# Breakout.net
KiCad netlist of a schematic drawn in Altium Designer
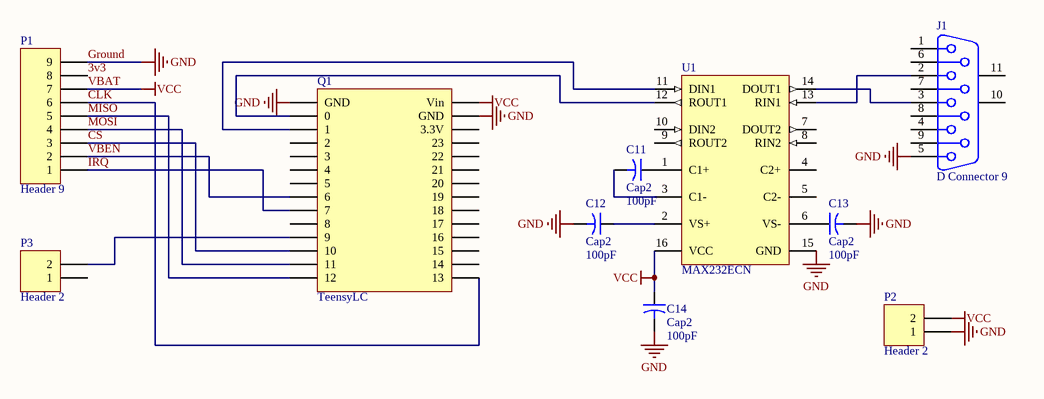
[diagram p0: Breakout.SchDoc]

(export (version "E")
  (design (tool "Eeschema 10.0.6"))
  (components
    (comp (ref "C11")
      (value "Cap2")
      (footprint "CAPR5-4X5")
      (description "Capacitor")
      (fields (field (name "ALTIUM_VALUE") "100pF") (field (name "PUBLISHER") "Altium Limited"))
      (libsource (lib "Miscellaneous Devices") (part "Cap2"))
    )
    (comp (ref "C12")
      (value "Cap2")
      (footprint "CAPR5-4X5")
      (description "Capacitor")
      (fields (field (name "ALTIUM_VALUE") "100pF") (field (name "PUBLISHER") "Altium Limited"))
      (libsource (lib "Miscellaneous Devices") (part "Cap2"))
    )
    (comp (ref "C13")
      (value "Cap2")
      (footprint "CAPR5-4X5")
      (description "Capacitor")
      (fields (field (name "ALTIUM_VALUE") "100pF") (field (name "PUBLISHER") "Altium Limited"))
      (libsource (lib "Miscellaneous Devices") (part "Cap2"))
    )
    (comp (ref "C14")
      (value "Cap2")
      (footprint "CAPR5-4X5")
      (description "Capacitor")
      (fields (field (name "ALTIUM_VALUE") "100pF") (field (name "PUBLISHER") "Altium Limited"))
      (libsource (lib "Miscellaneous Devices") (part "Cap2"))
    )
    (comp (ref "J1")
      (value "D Connector 9")
      (footprint "DSUB1.385-2H9")
      (description "Receptacle Assembly, 9 Position, Right Angle")
      (fields (field (name "PUBLISHER") "Altium Limited"))
      (libsource (lib "Miscellaneous Connectors") (part "D Connector 9"))
    )
    (comp (ref "P1")
      (value "Header 9")
      (footprint "HDR1X9")
      (description "Header, 9-Pin")
      (fields (field (name "PUBLISHER") "Altium Limited"))
      (libsource (lib "Miscellaneous Connectors") (part "Header 9"))
    )
    (comp (ref "P2")
      (value "Header 2")
      (footprint "HDR1X2")
      (description "Header, 2-Pin")
      (fields (field (name "PUBLISHER") "Altium Limited"))
      (libsource (lib "Miscellaneous Connectors") (part "Header 2"))
    )
    (comp (ref "P3")
      (value "Header 2")
      (footprint "HDR1X2")
      (description "Header, 2-Pin")
      (fields (field (name "PUBLISHER") "Altium Limited"))
      (libsource (lib "Miscellaneous Connectors") (part "Header 2"))
    )
    (comp (ref "Q1")
      (value "TeensyLC")
      (footprint "TeensyLC")
      (libsource (lib "Custom_Components") (part "TeensyLC"))
    )
    (comp (ref "U1")
      (value "MAX232ECN")
      (footprint "TI-N16")
      (libsource (lib "Texas Instruments Interface RS-232") (part "MAX232ECN"))
    )
  )
  (nets
    (net (code "1") (name "/3v3") (class "Default")
      (node (ref "P1") (pin "8") (pinfunction "8_8") (pintype "passive"))
    )
    (net (code "2") (name "/CLK") (class "Default")
      (node (ref "P1") (pin "6") (pinfunction "6_6") (pintype "passive"))
      (node (ref "Q1") (pin "15") (pinfunction "13_15") (pintype "passive"))
    )
    (net (code "3") (name "/CS") (class "Default")
      (node (ref "P1") (pin "3") (pinfunction "3_3") (pintype "passive"))
      (node (ref "Q1") (pin "12") (pinfunction "10_12") (pintype "passive"))
    )
    (net (code "4") (name "/IRQ") (class "Default")
      (node (ref "P1") (pin "1") (pinfunction "1_1") (pintype "passive"))
      (node (ref "Q1") (pin "9") (pinfunction "7_9") (pintype "passive"))
    )
    (net (code "5") (name "/MISO") (class "Default")
      (node (ref "P1") (pin "5") (pinfunction "5_5") (pintype "passive"))
      (node (ref "Q1") (pin "14") (pinfunction "12_14") (pintype "passive"))
    )
    (net (code "6") (name "/MOSI") (class "Default")
      (node (ref "P1") (pin "4") (pinfunction "4_4") (pintype "passive"))
      (node (ref "Q1") (pin "13") (pinfunction "11_13") (pintype "passive"))
    )
    (net (code "7") (name "/VBEN") (class "Default")
      (node (ref "P1") (pin "2") (pinfunction "2_2") (pintype "passive"))
      (node (ref "Q1") (pin "8") (pinfunction "6_8") (pintype "passive"))
    )
    (net (code "8") (name "GND") (class "Default")
      (node (ref "C12") (pin "2") (pinfunction "2_2") (pintype "passive"))
      (node (ref "C13") (pin "2") (pinfunction "2_2") (pintype "passive"))
      (node (ref "C14") (pin "2") (pinfunction "2_2") (pintype "passive"))
      (node (ref "J1") (pin "5") (pinfunction "5_5") (pintype "passive"))
      (node (ref "P1") (pin "9") (pinfunction "9_9") (pintype "passive"))
      (node (ref "P2") (pin "1") (pinfunction "1_1") (pintype "passive"))
      (node (ref "Q1") (pin "1") (pinfunction "GND_1") (pintype "passive"))
      (node (ref "Q1") (pin "27") (pinfunction "GND_27") (pintype "passive"))
      (node (ref "U1") (pin "15") (pinfunction "GND_15") (pintype "power_in"))
    )
    (net (code "9") (name "Net-(Q1-0)") (class "Default")
      (node (ref "Q1") (pin "2") (pinfunction "0_2") (pintype "passive"))
      (node (ref "U1") (pin "12") (pinfunction "ROUT1_12") (pintype "output"))
    )
    (net (code "10") (name "Net-(Q1-1)") (class "Default")
      (node (ref "Q1") (pin "3") (pinfunction "1_3") (pintype "passive"))
      (node (ref "U1") (pin "11") (pinfunction "DIN1_11") (pintype "input"))
    )
    (net (code "11") (name "Net-(Q1-9)") (class "Default")
      (node (ref "P3") (pin "2") (pinfunction "2_2") (pintype "passive"))
      (node (ref "Q1") (pin "11") (pinfunction "9_11") (pintype "passive"))
    )
    (net (code "12") (name "Net-(U1-C1+)") (class "Default")
      (node (ref "C11") (pin "1") (pinfunction "1_1") (pintype "passive"))
      (node (ref "U1") (pin "1") (pinfunction "C1+_1") (pintype "passive"))
    )
    (net (code "13") (name "Net-(U1-C1-)") (class "Default")
      (node (ref "C11") (pin "2") (pinfunction "2_2") (pintype "passive"))
      (node (ref "U1") (pin "3") (pinfunction "C1-_3") (pintype "passive"))
    )
    (net (code "14") (name "Net-(U1-DOUT1)") (class "Default")
      (node (ref "J1") (pin "3") (pinfunction "3_3") (pintype "passive"))
      (node (ref "U1") (pin "14") (pinfunction "DOUT1_14") (pintype "output"))
    )
    (net (code "15") (name "Net-(U1-RIN1)") (class "Default")
      (node (ref "J1") (pin "2") (pinfunction "2_2") (pintype "passive"))
      (node (ref "U1") (pin "13") (pinfunction "RIN1_13") (pintype "input"))
    )
    (net (code "16") (name "Net-(U1-VS+)") (class "Default")
      (node (ref "C12") (pin "1") (pinfunction "1_1") (pintype "passive"))
      (node (ref "U1") (pin "2") (pinfunction "VS+_2") (pintype "power_in"))
    )
    (net (code "17") (name "Net-(U1-VS-)") (class "Default")
      (node (ref "C13") (pin "1") (pinfunction "1_1") (pintype "passive"))
      (node (ref "U1") (pin "6") (pinfunction "VS-_6") (pintype "power_in"))
    )
    (net (code "18") (name "VCC") (class "Default")
      (node (ref "C14") (pin "1") (pinfunction "1_1") (pintype "passive"))
      (node (ref "P1") (pin "7") (pinfunction "7_7") (pintype "passive"))
      (node (ref "P2") (pin "2") (pinfunction "2_2") (pintype "passive"))
      (node (ref "Q1") (pin "28") (pinfunction "Vin_28") (pintype "passive"))
      (node (ref "U1") (pin "16") (pinfunction "VCC_16") (pintype "power_in"))
    )
    (net (code "19") (name "unconnected-(J1-MH1-Pad10)") (class "Default")
      (node (ref "J1") (pin "10") (pinfunction "MH1_10") (pintype "passive"))
    )
    (net (code "20") (name "unconnected-(J1-MH2-Pad11)") (class "Default")
      (node (ref "J1") (pin "11") (pinfunction "MH2_11") (pintype "passive"))
    )
    (net (code "21") (name "unconnected-(J1-Pad1)") (class "Default")
      (node (ref "J1") (pin "1") (pinfunction "1_1") (pintype "passive"))
    )
    (net (code "22") (name "unconnected-(J1-Pad4)") (class "Default")
      (node (ref "J1") (pin "4") (pinfunction "4_4") (pintype "passive"))
    )
    (net (code "23") (name "unconnected-(J1-Pad6)") (class "Default")
      (node (ref "J1") (pin "6") (pinfunction "6_6") (pintype "passive"))
    )
    (net (code "24") (name "unconnected-(J1-Pad7)") (class "Default")
      (node (ref "J1") (pin "7") (pinfunction "7_7") (pintype "passive"))
    )
    (net (code "25") (name "unconnected-(J1-Pad8)") (class "Default")
      (node (ref "J1") (pin "8") (pinfunction "8_8") (pintype "passive"))
    )
    (net (code "26") (name "unconnected-(J1-Pad9)") (class "Default")
      (node (ref "J1") (pin "9") (pinfunction "9_9") (pintype "passive"))
    )
    (net (code "27") (name "unconnected-(P3-Pad1)") (class "Default")
      (node (ref "P3") (pin "1") (pinfunction "1_1") (pintype "passive"))
    )
    (net (code "28") (name "unconnected-(Q1-2-Pad4)") (class "Default")
      (node (ref "Q1") (pin "4") (pinfunction "2_4") (pintype "passive"))
    )
    (net (code "29") (name "unconnected-(Q1-3-Pad5)") (class "Default")
      (node (ref "Q1") (pin "5") (pinfunction "3_5") (pintype "passive"))
    )
    (net (code "30") (name "unconnected-(Q1-3.3V-Pad26)") (class "Default")
      (node (ref "Q1") (pin "26") (pinfunction "3.3V_26") (pintype "passive"))
    )
    (net (code "31") (name "unconnected-(Q1-4-Pad6)") (class "Default")
      (node (ref "Q1") (pin "6") (pinfunction "4_6") (pintype "passive"))
    )
    (net (code "32") (name "unconnected-(Q1-5-Pad7)") (class "Default")
      (node (ref "Q1") (pin "7") (pinfunction "5_7") (pintype "passive"))
    )
    (net (code "33") (name "unconnected-(Q1-8-Pad10)") (class "Default")
      (node (ref "Q1") (pin "10") (pinfunction "8_10") (pintype "passive"))
    )
    (net (code "34") (name "unconnected-(Q1-14-Pad16)") (class "Default")
      (node (ref "Q1") (pin "16") (pinfunction "14_16") (pintype "passive"))
    )
    (net (code "35") (name "unconnected-(Q1-15-Pad17)") (class "Default")
      (node (ref "Q1") (pin "17") (pinfunction "15_17") (pintype "passive"))
    )
    (net (code "36") (name "unconnected-(Q1-16-Pad18)") (class "Default")
      (node (ref "Q1") (pin "18") (pinfunction "16_18") (pintype "passive"))
    )
    (net (code "37") (name "unconnected-(Q1-17-Pad19)") (class "Default")
      (node (ref "Q1") (pin "19") (pinfunction "17_19") (pintype "passive"))
    )
    (net (code "38") (name "unconnected-(Q1-18-Pad20)") (class "Default")
      (node (ref "Q1") (pin "20") (pinfunction "18_20") (pintype "passive"))
    )
    (net (code "39") (name "unconnected-(Q1-19-Pad21)") (class "Default")
      (node (ref "Q1") (pin "21") (pinfunction "19_21") (pintype "passive"))
    )
    (net (code "40") (name "unconnected-(Q1-20-Pad22)") (class "Default")
      (node (ref "Q1") (pin "22") (pinfunction "20_22") (pintype "passive"))
    )
    (net (code "41") (name "unconnected-(Q1-21-Pad23)") (class "Default")
      (node (ref "Q1") (pin "23") (pinfunction "21_23") (pintype "passive"))
    )
    (net (code "42") (name "unconnected-(Q1-22-Pad24)") (class "Default")
      (node (ref "Q1") (pin "24") (pinfunction "22_24") (pintype "passive"))
    )
    (net (code "43") (name "unconnected-(Q1-23-Pad25)") (class "Default")
      (node (ref "Q1") (pin "25") (pinfunction "23_25") (pintype "passive"))
    )
    (net (code "44") (name "unconnected-(U1-C2+-Pad4)") (class "Default")
      (node (ref "U1") (pin "4") (pinfunction "C2+_4") (pintype "passive"))
    )
    (net (code "45") (name "unconnected-(U1-C2--Pad5)") (class "Default")
      (node (ref "U1") (pin "5") (pinfunction "C2-_5") (pintype "passive"))
    )
    (net (code "46") (name "unconnected-(U1-DIN2-Pad10)") (class "Default")
      (node (ref "U1") (pin "10") (pinfunction "DIN2_10") (pintype "input"))
    )
    (net (code "47") (name "unconnected-(U1-DOUT2-Pad7)") (class "Default")
      (node (ref "U1") (pin "7") (pinfunction "DOUT2_7") (pintype "output"))
    )
    (net (code "48") (name "unconnected-(U1-RIN2-Pad8)") (class "Default")
      (node (ref "U1") (pin "8") (pinfunction "RIN2_8") (pintype "input"))
    )
    (net (code "49") (name "unconnected-(U1-ROUT2-Pad9)") (class "Default")
      (node (ref "U1") (pin "9") (pinfunction "ROUT2_9") (pintype "output"))
    )
  )
)
